# V0p2_Main_PCB2.net
KiCad netlist of a schematic drawn in EAGLE
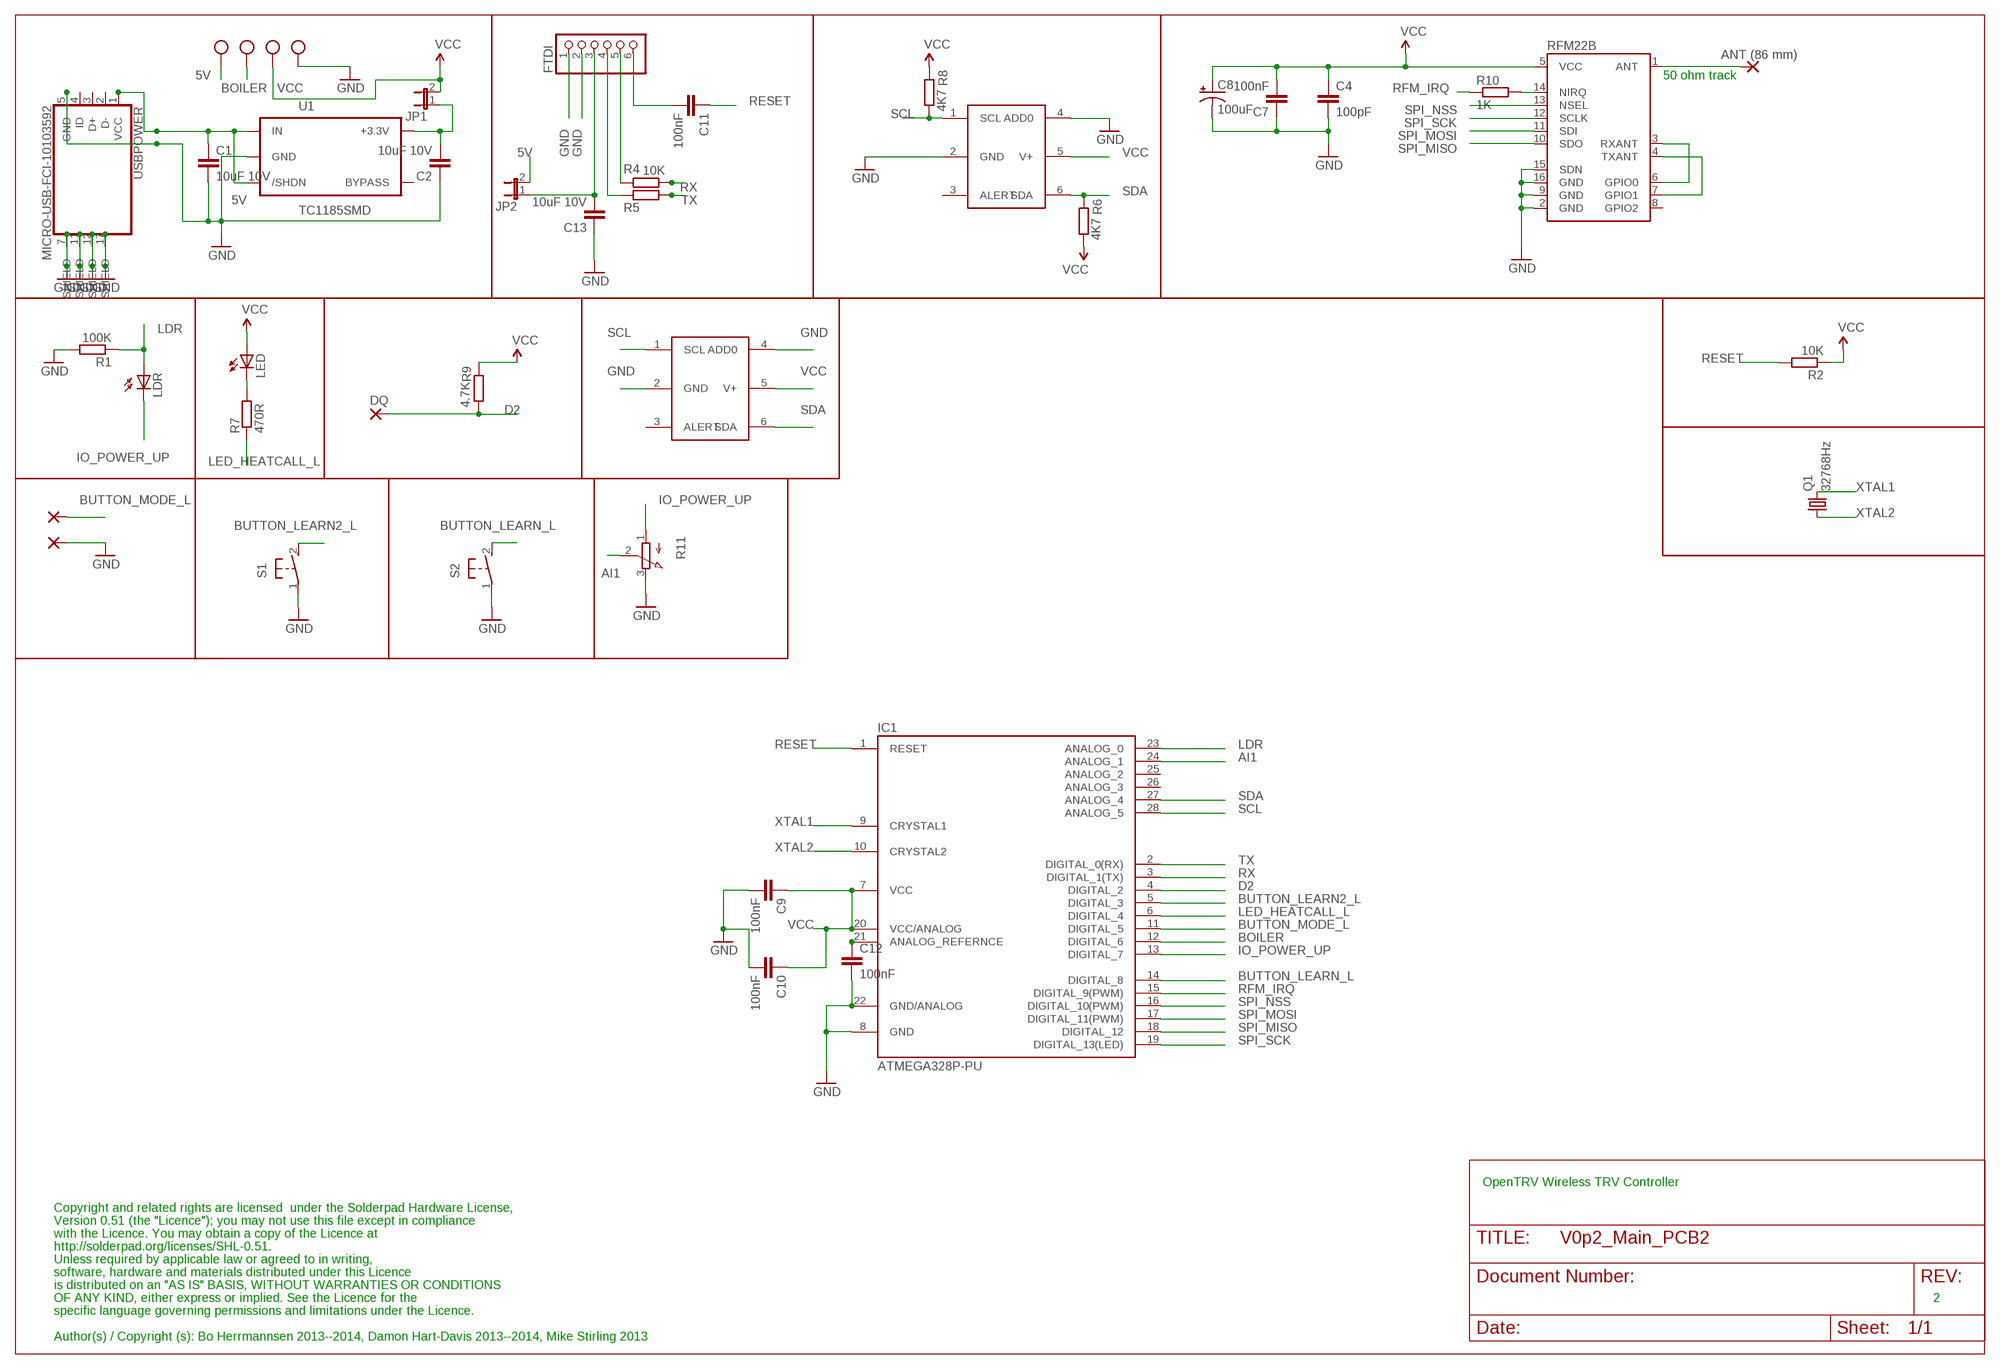
[diagram p0: schematic, sheet 1]

(export (version "E")
  (design (tool "Eeschema 10.0.6"))
  (components
    (comp (ref "ANT")
      (value "ANT (86 mm)")
      (footprint "eagle-import:2,15_1,0")
      (libsource (lib "eagle-import") (part "2,15/1,0"))
    )
    (comp (ref "C1")
      (value "10uF 10V")
      (footprint "eagle-import:0603-CAP")
      (libsource (lib "eagle-import") (part "CAP0603-CAP"))
    )
    (comp (ref "C2")
      (value "10uF 10V")
      (footprint "eagle-import:0603-CAP")
      (libsource (lib "eagle-import") (part "CAP0603-CAP"))
    )
    (comp (ref "C4")
      (value "100pF")
      (footprint "eagle-import:0603-CAP")
      (libsource (lib "eagle-import") (part "CAP0603-CAP"))
    )
    (comp (ref "C7")
      (value "100nF")
      (footprint "eagle-import:0603-CAP")
      (libsource (lib "eagle-import") (part "CAP0603-CAP"))
    )
    (comp (ref "C8")
      (value "100uF")
      (footprint "eagle-import:EIA3216")
      (libsource (lib "eagle-import") (part "CAP_POL1206"))
    )
    (comp (ref "C9")
      (value "100nF")
      (footprint "eagle-import:0603-CAP")
      (libsource (lib "eagle-import") (part "CAP0603-CAP"))
    )
    (comp (ref "C10")
      (value "100nF")
      (footprint "eagle-import:0603-CAP")
      (libsource (lib "eagle-import") (part "CAP0603-CAP"))
    )
    (comp (ref "C11")
      (value "100nF")
      (footprint "eagle-import:0603-CAP")
      (libsource (lib "eagle-import") (part "CAP0603-CAP"))
    )
    (comp (ref "C12")
      (value "100nF")
      (footprint "eagle-import:0603-CAP")
      (libsource (lib "eagle-import") (part "CAP0603-CAP"))
    )
    (comp (ref "C13")
      (value "10uF 10V")
      (footprint "eagle-import:0603-CAP")
      (libsource (lib "eagle-import") (part "CAP0603-CAP"))
    )
    (comp (ref "DQ")
      (value "2,15/1,0")
      (footprint "eagle-import:2,15_1,0")
      (libsource (lib "eagle-import") (part "2,15/1,0"))
    )
    (comp (ref "FTDI")
      (value "PINHD-1X6/90")
      (footprint "eagle-import:1X06_90")
      (libsource (lib "eagle-import") (part "PINHD-1X6/90"))
    )
    (comp (ref "IC1")
      (value "ATMEGA328P-PU")
      (footprint "eagle-import:DIL28-3")
      (libsource (lib "eagle-import") (part "ATMEGA8-PU"))
    )
    (comp (ref "JP1")
      (value "JP1E")
      (footprint "eagle-import:JP1")
      (libsource (lib "eagle-import") (part "JP1E"))
    )
    (comp (ref "JP2")
      (value "JP1E")
      (footprint "eagle-import:JP1")
      (libsource (lib "eagle-import") (part "JP1E"))
    )
    (comp (ref "LDR")
      (value "BPX65")
      (footprint "eagle-import:BPX65")
      (fields (field (name "MPN") "BPX65."))
      (libsource (lib "eagle-import") (part "BPX65"))
    )
    (comp (ref "LED")
      (value "LED3MM")
      (footprint "eagle-import:LED3MM")
      (libsource (lib "eagle-import") (part "LED3MM"))
    )
    (comp (ref "MODE")
      (value "2,15/1,0")
      (footprint "eagle-import:2,15_1,0")
      (libsource (lib "eagle-import") (part "2,15/1,0"))
    )
    (comp (ref "MODE1")
      (value "2,15/1,0")
      (footprint "eagle-import:2,15_1,0")
      (libsource (lib "eagle-import") (part "2,15/1,0"))
    )
    (comp (ref "Q1")
      (value "32768Hz")
      (footprint "eagle-import:MC-306")
      (fields (field (name "MPN") "MC-306 60.0KHZ  100PPM ,12.5PF"))
      (libsource (lib "eagle-import") (part "MC-306"))
    )
    (comp (ref "R1")
      (value "100K")
      (footprint "eagle-import:R0603")
      (libsource (lib "eagle-import") (part "R-EU_R0603"))
    )
    (comp (ref "R2")
      (value "10K")
      (footprint "eagle-import:R0603")
      (libsource (lib "eagle-import") (part "R-EU_R0603"))
    )
    (comp (ref "R4")
      (value "10K")
      (footprint "eagle-import:R0603")
      (libsource (lib "eagle-import") (part "R-EU_R0603"))
    )
    (comp (ref "R5")
      (value "10K")
      (footprint "eagle-import:R0603")
      (libsource (lib "eagle-import") (part "R-EU_R0603"))
    )
    (comp (ref "R6")
      (value "4K7")
      (footprint "eagle-import:R0603")
      (libsource (lib "eagle-import") (part "R-EU_R0603"))
    )
    (comp (ref "R7")
      (value "470R")
      (footprint "eagle-import:R0603")
      (libsource (lib "eagle-import") (part "R-EU_R0603"))
    )
    (comp (ref "R8")
      (value "4K7")
      (footprint "eagle-import:R0603")
      (libsource (lib "eagle-import") (part "R-EU_R0603"))
    )
    (comp (ref "R9")
      (value "4.7K")
      (footprint "eagle-import:R0603")
      (libsource (lib "eagle-import") (part "R-EU_R0603"))
    )
    (comp (ref "R10")
      (value "1K")
      (footprint "eagle-import:R0603")
      (libsource (lib "eagle-import") (part "R-EU_R0603"))
    )
    (comp (ref "R11")
      (value "EVUE2A")
      (footprint "eagle-import:EVUE")
      (libsource (lib "eagle-import") (part "EVUE2A"))
    )
    (comp (ref "RFM22B")
      (value "RFM22SMD")
      (footprint "eagle-import:RFM22-XXX-S2")
      (libsource (lib "eagle-import") (part "RFM22SMD"))
    )
    (comp (ref "S1")
      (value "31-XX")
      (footprint "eagle-import:B3F-31XX")
      (libsource (lib "eagle-import") (part "31-XX"))
    )
    (comp (ref "S2")
      (value "31-XX")
      (footprint "eagle-import:B3F-31XX")
      (libsource (lib "eagle-import") (part "31-XX"))
    )
    (comp (ref "TMP1")
      (value "TMP1")
      (footprint "eagle-import:TMP112")
      (libsource (lib "eagle-import") (part "TMP112"))
    )
    (comp (ref "TMP2")
      (value "TMP2")
      (footprint "eagle-import:TMP112")
      (libsource (lib "eagle-import") (part "TMP112_2_TMP112"))
    )
    (comp (ref "U1")
      (value "TC1185SMD")
      (footprint "eagle-import:TC1185")
      (libsource (lib "eagle-import") (part "TC1185SMD"))
    )
    (comp (ref "USBPOWER")
      (value "MICRO-USB-FCI-10103592")
      (footprint "eagle-import:MICRO-USB-FCI-10103592")
      (libsource (lib "eagle-import") (part "MICRO-USB-FCI-10103592"))
    )
    (comp (ref "X1")
      (value "W237-102")
      (footprint "eagle-import:SCREWTERMINAL")
      (fields (field (name "MPN") "237-102"))
      (libsource (lib "eagle-import") (part "W237-102"))
    )
    (comp (ref "X2")
      (value "W237-102")
      (footprint "eagle-import:SCREWTERMINAL")
      (fields (field (name "MPN") "237-102"))
      (libsource (lib "eagle-import") (part "W237-102"))
    )
  )
  (nets
    (net (code "1") (name "/5V") (class "Default")
      (node (ref "C1") (pin "1") (pinfunction "1_1") (pintype "passive"))
      (node (ref "JP2") (pin "2") (pinfunction "2_2") (pintype "passive"))
      (node (ref "U1") (pin "1") (pinfunction "IN_1") (pintype "passive"))
      (node (ref "U1") (pin "3") (pinfunction "/SHDN_3") (pintype "passive"))
      (node (ref "USBPOWER") (pin "1") (pinfunction "VCC_1") (pintype "bidirectional"))
      (node (ref "X1") (pin "2") (pinfunction "KL_2") (pintype "passive"))
    )
    (net (code "2") (name "/AI1") (class "Default")
      (node (ref "IC1") (pin "24") (pinfunction "ANALOG_1_24") (pintype "bidirectional"))
      (node (ref "R11") (pin "2") (pinfunction "S_2") (pintype "passive"))
    )
    (net (code "3") (name "/BOILER") (class "Default")
      (node (ref "IC1") (pin "12") (pinfunction "DIGITAL_6_12") (pintype "bidirectional"))
      (node (ref "X1") (pin "1") (pinfunction "KL_1") (pintype "passive"))
    )
    (net (code "4") (name "/BUTTON_LEARN2_L") (class "Default")
      (node (ref "IC1") (pin "5") (pinfunction "DIGITAL_3_5") (pintype "bidirectional"))
      (node (ref "S1") (pin "2") (pinfunction "S_2") (pintype "passive"))
    )
    (net (code "5") (name "/BUTTON_LEARN_L") (class "Default")
      (node (ref "IC1") (pin "14") (pinfunction "DIGITAL_8_14") (pintype "bidirectional"))
      (node (ref "S2") (pin "2") (pinfunction "S_2") (pintype "passive"))
    )
    (net (code "6") (name "/BUTTON_MODE_L") (class "Default")
      (node (ref "IC1") (pin "11") (pinfunction "DIGITAL_5_11") (pintype "bidirectional"))
      (node (ref "MODE1") (pin "1") (pinfunction "P_1") (pintype "passive"))
    )
    (net (code "7") (name "/D2") (class "Default")
      (node (ref "DQ") (pin "1") (pinfunction "P_1") (pintype "passive"))
      (node (ref "IC1") (pin "4") (pinfunction "DIGITAL_2_4") (pintype "bidirectional"))
      (node (ref "R9") (pin "1") (pinfunction "1_1") (pintype "passive"))
    )
    (net (code "8") (name "/IO_POWER_UP") (class "Default")
      (node (ref "IC1") (pin "13") (pinfunction "DIGITAL_7_13") (pintype "bidirectional"))
      (node (ref "LDR") (pin "K") (pinfunction "C_K") (pintype "passive"))
      (node (ref "R11") (pin "1") (pinfunction "A_1") (pintype "passive"))
    )
    (net (code "9") (name "/LDR") (class "Default")
      (node (ref "IC1") (pin "23") (pinfunction "ANALOG_0_23") (pintype "bidirectional"))
      (node (ref "LDR") (pin "A") (pinfunction "A_A") (pintype "passive"))
      (node (ref "R1") (pin "1") (pinfunction "1_1") (pintype "passive"))
    )
    (net (code "10") (name "/LED_HEATCALL_L") (class "Default")
      (node (ref "IC1") (pin "6") (pinfunction "DIGITAL_4_6") (pintype "bidirectional"))
      (node (ref "R7") (pin "1") (pinfunction "1_1") (pintype "passive"))
    )
    (net (code "11") (name "/RESET") (class "Default")
      (node (ref "C11") (pin "1") (pinfunction "1_1") (pintype "passive"))
      (node (ref "IC1") (pin "1") (pinfunction "RESET_1") (pintype "bidirectional"))
      (node (ref "R2") (pin "2") (pinfunction "2_2") (pintype "passive"))
    )
    (net (code "12") (name "/RFM_IRQ") (class "Default")
      (node (ref "IC1") (pin "15") (pinfunction "DIGITAL_9(PWM)_15") (pintype "bidirectional"))
      (node (ref "R10") (pin "1") (pinfunction "1_1") (pintype "passive"))
    )
    (net (code "13") (name "/RX") (class "Default")
      (node (ref "IC1") (pin "3") (pinfunction "DIGITAL_1(TX)_3") (pintype "bidirectional"))
      (node (ref "R4") (pin "1") (pinfunction "1_1") (pintype "passive"))
    )
    (net (code "14") (name "/SCL") (class "Default")
      (node (ref "IC1") (pin "28") (pinfunction "ANALOG_5_28") (pintype "bidirectional"))
      (node (ref "R8") (pin "1") (pinfunction "1_1") (pintype "passive"))
      (node (ref "TMP1") (pin "1") (pinfunction "SCL_1") (pintype "bidirectional"))
      (node (ref "TMP2") (pin "1") (pinfunction "SCL_1") (pintype "bidirectional"))
    )
    (net (code "15") (name "/SDA") (class "Default")
      (node (ref "IC1") (pin "27") (pinfunction "ANALOG_4_27") (pintype "bidirectional"))
      (node (ref "R6") (pin "2") (pinfunction "2_2") (pintype "passive"))
      (node (ref "TMP1") (pin "6") (pinfunction "SDA_6") (pintype "bidirectional"))
      (node (ref "TMP2") (pin "6") (pinfunction "SDA_6") (pintype "bidirectional"))
    )
    (net (code "16") (name "/SPI_MISO") (class "Default")
      (node (ref "IC1") (pin "18") (pinfunction "DIGITAL_12_18") (pintype "bidirectional"))
      (node (ref "RFM22B") (pin "10") (pinfunction "SDO_10") (pintype "output"))
    )
    (net (code "17") (name "/SPI_MOSI") (class "Default")
      (node (ref "IC1") (pin "17") (pinfunction "DIGITAL_11(PWM)_17") (pintype "bidirectional"))
      (node (ref "RFM22B") (pin "11") (pinfunction "SDI_11") (pintype "input"))
    )
    (net (code "18") (name "/SPI_NSS") (class "Default")
      (node (ref "IC1") (pin "16") (pinfunction "DIGITAL_10(PWM)_16") (pintype "bidirectional"))
      (node (ref "RFM22B") (pin "13") (pinfunction "NSEL_13") (pintype "input"))
    )
    (net (code "19") (name "/SPI_SCK") (class "Default")
      (node (ref "IC1") (pin "19") (pinfunction "DIGITAL_13(LED)_19") (pintype "bidirectional"))
      (node (ref "RFM22B") (pin "12") (pinfunction "SCLK_12") (pintype "input"))
    )
    (net (code "20") (name "/TX") (class "Default")
      (node (ref "IC1") (pin "2") (pinfunction "DIGITAL_0(RX)_2") (pintype "bidirectional"))
      (node (ref "R5") (pin "1") (pinfunction "1_1") (pintype "passive"))
    )
    (net (code "21") (name "/XTAL1") (class "Default")
      (node (ref "IC1") (pin "9") (pinfunction "CRYSTAL1_9") (pintype "bidirectional"))
      (node (ref "Q1") (pin "4") (pinfunction "2_4") (pintype "passive"))
    )
    (net (code "22") (name "/XTAL2") (class "Default")
      (node (ref "IC1") (pin "10") (pinfunction "CRYSTAL2_10") (pintype "bidirectional"))
      (node (ref "Q1") (pin "1") (pinfunction "1_1") (pintype "passive"))
    )
    (net (code "23") (name "GND") (class "Default")
      (node (ref "C1") (pin "2") (pinfunction "2_2") (pintype "passive"))
      (node (ref "C10") (pin "2") (pinfunction "2_2") (pintype "passive"))
      (node (ref "C12") (pin "2") (pinfunction "2_2") (pintype "passive"))
      (node (ref "C13") (pin "1") (pinfunction "1_1") (pintype "passive"))
      (node (ref "C2") (pin "1") (pinfunction "1_1") (pintype "passive"))
      (node (ref "C4") (pin "2") (pinfunction "2_2") (pintype "passive"))
      (node (ref "C7") (pin "1") (pinfunction "1_1") (pintype "passive"))
      (node (ref "C8") (pin "C") (pinfunction "-_C") (pintype "passive"))
      (node (ref "C9") (pin "2") (pinfunction "2_2") (pintype "passive"))
      (node (ref "FTDI") (pin "1") (pinfunction "1_1") (pintype "passive"))
      (node (ref "FTDI") (pin "2") (pinfunction "2_2") (pintype "passive"))
      (node (ref "IC1") (pin "22") (pinfunction "GND/ANALOG_22") (pintype "power_in"))
      (node (ref "IC1") (pin "8") (pinfunction "GND_8") (pintype "power_in"))
      (node (ref "MODE") (pin "1") (pinfunction "P_1") (pintype "passive"))
      (node (ref "R1") (pin "2") (pinfunction "2_2") (pintype "passive"))
      (node (ref "R11") (pin "3") (pinfunction "E_3") (pintype "passive"))
      (node (ref "RFM22B") (pin "15") (pinfunction "SDN_15") (pintype "input"))
      (node (ref "RFM22B") (pin "16") (pinfunction "GND_16") (pintype "power_in"))
      (node (ref "RFM22B") (pin "2") (pinfunction "GND_2") (pintype "power_in"))
      (node (ref "RFM22B") (pin "9") (pinfunction "GND_9") (pintype "power_in"))
      (node (ref "S1") (pin "1") (pinfunction "P_1") (pintype "passive"))
      (node (ref "S2") (pin "1") (pinfunction "P_1") (pintype "passive"))
      (node (ref "TMP1") (pin "2") (pinfunction "GND_2") (pintype "bidirectional"))
      (node (ref "TMP1") (pin "4") (pinfunction "ADD0_4") (pintype "bidirectional"))
      (node (ref "TMP2") (pin "2") (pinfunction "GND_2") (pintype "bidirectional"))
      (node (ref "TMP2") (pin "4") (pinfunction "ADD0_4") (pintype "bidirectional"))
      (node (ref "U1") (pin "2") (pinfunction "GND_2") (pintype "passive"))
      (node (ref "USBPOWER") (pin "11") (pinfunction "SHIELD_11") (pintype "bidirectional"))
      (node (ref "USBPOWER") (pin "12") (pinfunction "SHIELD_12") (pintype "bidirectional"))
      (node (ref "USBPOWER") (pin "17") (pinfunction "SHIELD_17") (pintype "bidirectional"))
      (node (ref "USBPOWER") (pin "5") (pinfunction "GND_5") (pintype "bidirectional"))
      (node (ref "USBPOWER") (pin "7") (pinfunction "SHIELD_7") (pintype "bidirectional"))
      (node (ref "X2") (pin "2") (pinfunction "KL_2") (pintype "passive"))
    )
    (net (code "24") (name "Net-(ANT-P)") (class "Default")
      (node (ref "ANT") (pin "1") (pinfunction "P_1") (pintype "passive"))
      (node (ref "RFM22B") (pin "1") (pinfunction "ANT_1") (pintype "bidirectional"))
    )
    (net (code "25") (name "Net-(C11-Pad2)") (class "Default")
      (node (ref "C11") (pin "2") (pinfunction "2_2") (pintype "passive"))
      (node (ref "FTDI") (pin "6") (pinfunction "6_6") (pintype "passive"))
    )
    (net (code "26") (name "Net-(C13-Pad2)") (class "Default")
      (node (ref "C13") (pin "2") (pinfunction "2_2") (pintype "passive"))
      (node (ref "FTDI") (pin "3") (pinfunction "3_3") (pintype "passive"))
      (node (ref "JP2") (pin "1") (pinfunction "1_1") (pintype "passive"))
    )
    (net (code "27") (name "Net-(FTDI-Pad4)") (class "Default")
      (node (ref "FTDI") (pin "4") (pinfunction "4_4") (pintype "passive"))
      (node (ref "R5") (pin "2") (pinfunction "2_2") (pintype "passive"))
    )
    (net (code "28") (name "Net-(FTDI-Pad5)") (class "Default")
      (node (ref "FTDI") (pin "5") (pinfunction "5_5") (pintype "passive"))
      (node (ref "R4") (pin "2") (pinfunction "2_2") (pintype "passive"))
    )
    (net (code "29") (name "Net-(IC1-ANALOG_REFERNCE)") (class "Default")
      (node (ref "C12") (pin "1") (pinfunction "1_1") (pintype "passive"))
      (node (ref "IC1") (pin "21") (pinfunction "ANALOG_REFERNCE_21") (pintype "passive"))
    )
    (net (code "30") (name "Net-(LED-C)") (class "Default")
      (node (ref "LED") (pin "K") (pinfunction "C_K") (pintype "passive"))
      (node (ref "R7") (pin "2") (pinfunction "2_2") (pintype "passive"))
    )
    (net (code "31") (name "Net-(RFM22B-GPIO0)") (class "Default")
      (node (ref "RFM22B") (pin "3") (pinfunction "RXANT_3") (pintype "input"))
      (node (ref "RFM22B") (pin "6") (pinfunction "GPIO0_6") (pintype "bidirectional"))
    )
    (net (code "32") (name "Net-(RFM22B-GPIO1)") (class "Default")
      (node (ref "RFM22B") (pin "4") (pinfunction "TXANT_4") (pintype "input"))
      (node (ref "RFM22B") (pin "7") (pinfunction "GPIO1_7") (pintype "bidirectional"))
    )
    (net (code "33") (name "Net-(RFM22B-NIRQ)") (class "Default")
      (node (ref "R10") (pin "2") (pinfunction "2_2") (pintype "passive"))
      (node (ref "RFM22B") (pin "14") (pinfunction "NIRQ_14") (pintype "output"))
    )
    (net (code "34") (name "Net-(U1-+3.3V)") (class "Default")
      (node (ref "C2") (pin "2") (pinfunction "2_2") (pintype "passive"))
      (node (ref "JP1") (pin "1") (pinfunction "1_1") (pintype "passive"))
      (node (ref "U1") (pin "5") (pinfunction "+3.3V_5") (pintype "power_in"))
    )
    (net (code "35") (name "VCC") (class "Default")
      (node (ref "C10") (pin "1") (pinfunction "1_1") (pintype "passive"))
      (node (ref "C4") (pin "1") (pinfunction "1_1") (pintype "passive"))
      (node (ref "C7") (pin "2") (pinfunction "2_2") (pintype "passive"))
      (node (ref "C8") (pin "A") (pinfunction "+_A") (pintype "passive"))
      (node (ref "C9") (pin "1") (pinfunction "1_1") (pintype "passive"))
      (node (ref "IC1") (pin "20") (pinfunction "VCC/ANALOG_20") (pintype "passive"))
      (node (ref "IC1") (pin "7") (pinfunction "VCC_7") (pintype "power_in"))
      (node (ref "JP1") (pin "2") (pinfunction "2_2") (pintype "passive"))
      (node (ref "LED") (pin "A") (pinfunction "A_A") (pintype "passive"))
      (node (ref "R2") (pin "1") (pinfunction "1_1") (pintype "passive"))
      (node (ref "R6") (pin "1") (pinfunction "1_1") (pintype "passive"))
      (node (ref "R8") (pin "2") (pinfunction "2_2") (pintype "passive"))
      (node (ref "R9") (pin "2") (pinfunction "2_2") (pintype "passive"))
      (node (ref "RFM22B") (pin "5") (pinfunction "VCC_5") (pintype "bidirectional"))
      (node (ref "TMP1") (pin "5") (pinfunction "V+_5") (pintype "bidirectional"))
      (node (ref "TMP2") (pin "5") (pinfunction "V+_5") (pintype "bidirectional"))
      (node (ref "X2") (pin "1") (pinfunction "KL_1") (pintype "passive"))
    )
    (net (code "36") (name "unconnected-(IC1-ANALOG_2-Pad25)") (class "Default")
      (node (ref "IC1") (pin "25") (pinfunction "ANALOG_2_25") (pintype "bidirectional"))
    )
    (net (code "37") (name "unconnected-(IC1-ANALOG_3-Pad26)") (class "Default")
      (node (ref "IC1") (pin "26") (pinfunction "ANALOG_3_26") (pintype "bidirectional"))
    )
    (net (code "38") (name "unconnected-(RFM22B-GPIO2-Pad8)") (class "Default")
      (node (ref "RFM22B") (pin "8") (pinfunction "GPIO2_8") (pintype "bidirectional"))
    )
    (net (code "39") (name "unconnected-(TMP1-ALERT-Pad3)") (class "Default")
      (node (ref "TMP1") (pin "3") (pinfunction "ALERT_3") (pintype "bidirectional"))
    )
    (net (code "40") (name "unconnected-(TMP2-ALERT-Pad3)") (class "Default")
      (node (ref "TMP2") (pin "3") (pinfunction "ALERT_3") (pintype "bidirectional"))
    )
    (net (code "41") (name "unconnected-(U1-BYPASS-Pad4)") (class "Default")
      (node (ref "U1") (pin "4") (pinfunction "BYPASS_4") (pintype "passive"))
    )
    (net (code "42") (name "unconnected-(USBPOWER-D+-Pad3)") (class "Default")
      (node (ref "USBPOWER") (pin "3") (pinfunction "D+_3") (pintype "bidirectional"))
    )
    (net (code "43") (name "unconnected-(USBPOWER-D--Pad2)") (class "Default")
      (node (ref "USBPOWER") (pin "2") (pinfunction "D-_2") (pintype "bidirectional"))
    )
    (net (code "44") (name "unconnected-(USBPOWER-ID-Pad4)") (class "Default")
      (node (ref "USBPOWER") (pin "4") (pinfunction "ID_4") (pintype "bidirectional"))
    )
  )
)
